# pyboard.net
KiCad netlist of a schematic drawn in EAGLE
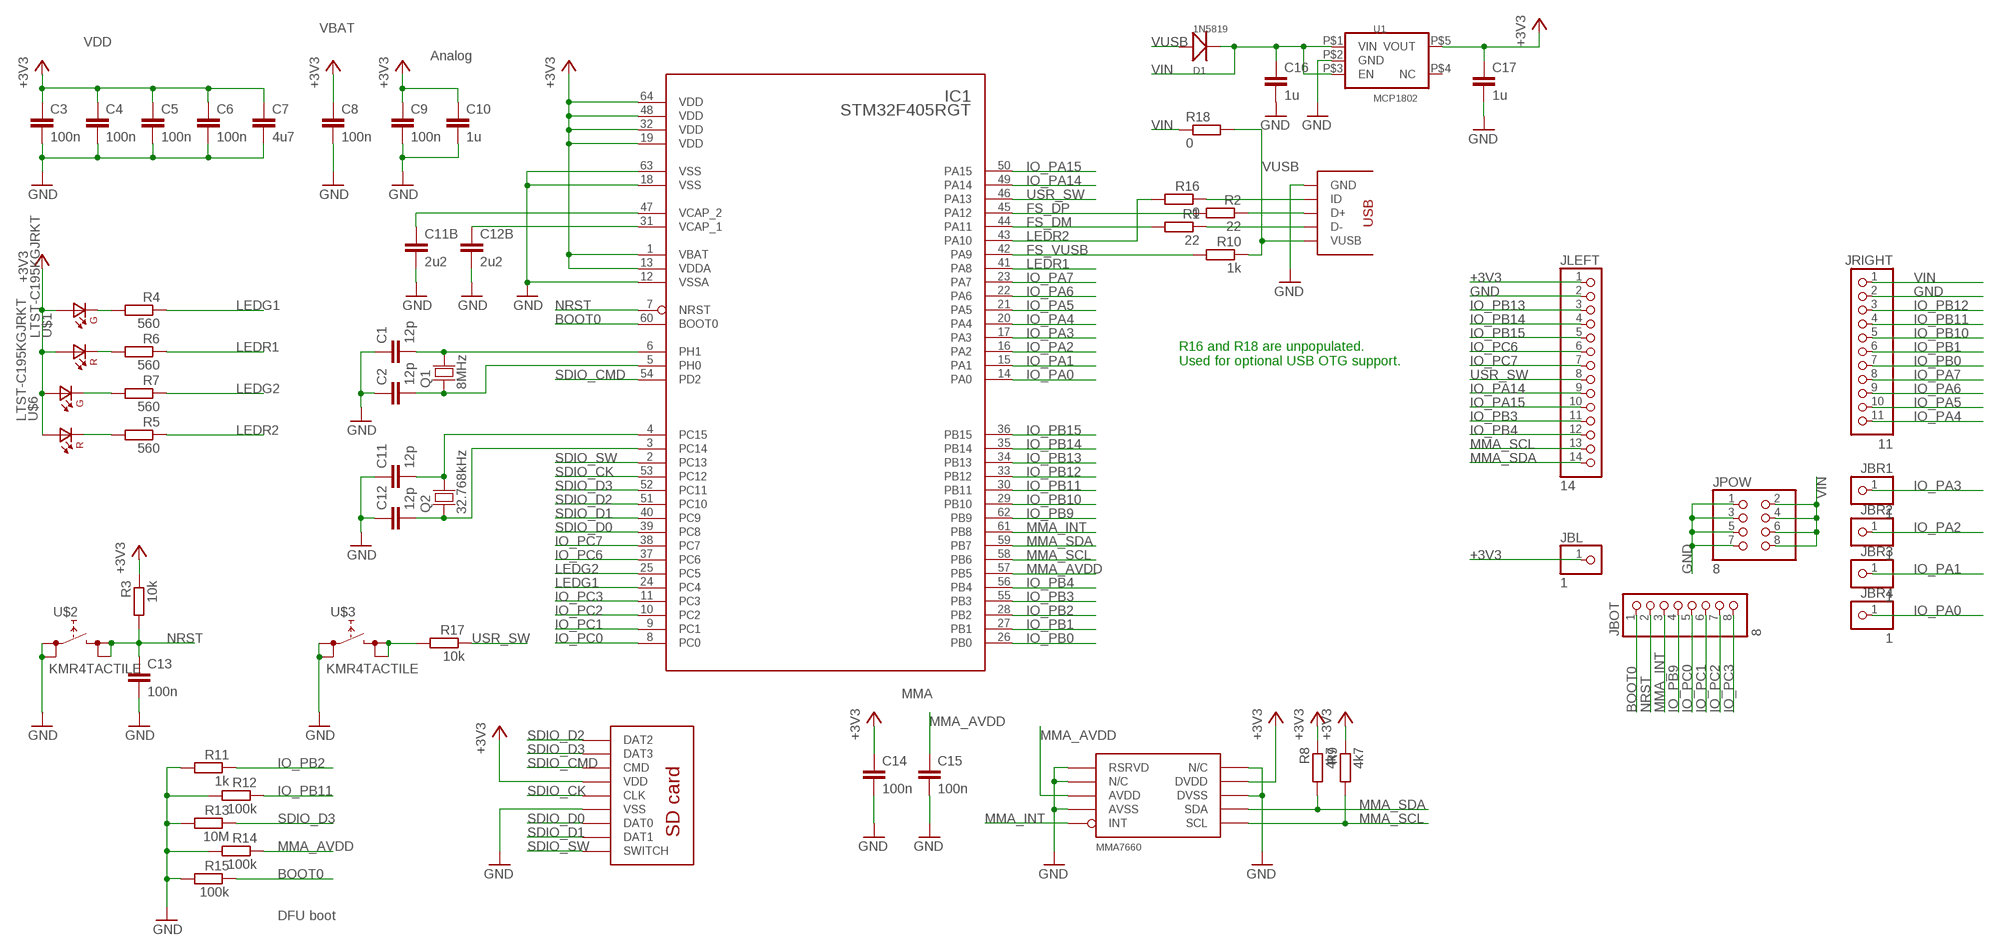
[diagram p0: schematic, sheet 1]

(export (version "E")
  (design (tool "Eeschema 10.0.6"))
  (components
    (comp (ref "C1")
      (value "12p")
      (footprint "eagle-import:C0603")
      (libsource (lib "eagle-import") (part "C-EUC0603"))
    )
    (comp (ref "C2")
      (value "12p")
      (footprint "eagle-import:C0603")
      (libsource (lib "eagle-import") (part "C-EUC0603"))
    )
    (comp (ref "C3")
      (value "100n")
      (footprint "eagle-import:C0603")
      (libsource (lib "eagle-import") (part "C-EUC0603"))
    )
    (comp (ref "C4")
      (value "100n")
      (footprint "eagle-import:C0603")
      (libsource (lib "eagle-import") (part "C-EUC0603"))
    )
    (comp (ref "C5")
      (value "100n")
      (footprint "eagle-import:C0603")
      (libsource (lib "eagle-import") (part "C-EUC0603"))
    )
    (comp (ref "C6")
      (value "100n")
      (footprint "eagle-import:C0603")
      (libsource (lib "eagle-import") (part "C-EUC0603"))
    )
    (comp (ref "C7")
      (value "4u7")
      (footprint "eagle-import:C0603")
      (libsource (lib "eagle-import") (part "C-EUC0603"))
    )
    (comp (ref "C8")
      (value "100n")
      (footprint "eagle-import:C0603")
      (libsource (lib "eagle-import") (part "C-EUC0603"))
    )
    (comp (ref "C9")
      (value "100n")
      (footprint "eagle-import:C0603")
      (libsource (lib "eagle-import") (part "C-EUC0603"))
    )
    (comp (ref "C10")
      (value "1u")
      (footprint "eagle-import:C0603")
      (libsource (lib "eagle-import") (part "C-EUC0603"))
    )
    (comp (ref "C11")
      (value "12p")
      (footprint "eagle-import:C0603")
      (libsource (lib "eagle-import") (part "C-EUC0603"))
    )
    (comp (ref "C11B")
      (value "2u2")
      (footprint "eagle-import:C0603")
      (libsource (lib "eagle-import") (part "C-EUC0603"))
    )
    (comp (ref "C12")
      (value "12p")
      (footprint "eagle-import:C0603")
      (libsource (lib "eagle-import") (part "C-EUC0603"))
    )
    (comp (ref "C12B")
      (value "2u2")
      (footprint "eagle-import:C0603")
      (libsource (lib "eagle-import") (part "C-EUC0603"))
    )
    (comp (ref "C13")
      (value "100n")
      (footprint "eagle-import:C0603")
      (libsource (lib "eagle-import") (part "C-EUC0603"))
    )
    (comp (ref "C14")
      (value "100n")
      (footprint "eagle-import:C0603")
      (libsource (lib "eagle-import") (part "C-EUC0603"))
    )
    (comp (ref "C15")
      (value "100n")
      (footprint "eagle-import:C0603")
      (libsource (lib "eagle-import") (part "C-EUC0603"))
    )
    (comp (ref "C16")
      (value "1u")
      (footprint "eagle-import:C0603")
      (libsource (lib "eagle-import") (part "C-EUC0603"))
    )
    (comp (ref "C17")
      (value "1u")
      (footprint "eagle-import:C0603")
      (libsource (lib "eagle-import") (part "C-EUC0603"))
    )
    (comp (ref "D1")
      (value "1N5819")
      (footprint "eagle-import:SOD-123")
      (libsource (lib "eagle-import") (part "1N5819"))
    )
    (comp (ref "IC1")
      (value "STM32F405RGT")
      (footprint "eagle-import:LQFP64")
      (libsource (lib "eagle-import") (part "STM32F405RTG"))
    )
    (comp (ref "JBL")
      (value "1")
      (footprint "eagle-import:1X01")
      (libsource (lib "eagle-import") (part "PINHD-1X1"))
    )
    (comp (ref "JBOT")
      (value "8")
      (footprint "eagle-import:1X08")
      (libsource (lib "eagle-import") (part "PINHD-1X8"))
    )
    (comp (ref "JBR1")
      (value "1")
      (footprint "eagle-import:1X01")
      (libsource (lib "eagle-import") (part "PINHD-1X1"))
    )
    (comp (ref "JBR2")
      (value "1")
      (footprint "eagle-import:1X01")
      (libsource (lib "eagle-import") (part "PINHD-1X1"))
    )
    (comp (ref "JBR3")
      (value "1")
      (footprint "eagle-import:1X01")
      (libsource (lib "eagle-import") (part "PINHD-1X1"))
    )
    (comp (ref "JBR4")
      (value "1")
      (footprint "eagle-import:1X01")
      (libsource (lib "eagle-import") (part "PINHD-1X1"))
    )
    (comp (ref "JLEFT")
      (value "14")
      (footprint "eagle-import:1X14")
      (libsource (lib "eagle-import") (part "PINHD-1X14"))
    )
    (comp (ref "JPOW")
      (value "8")
      (footprint "eagle-import:2X04")
      (libsource (lib "eagle-import") (part "PINHD-2X4"))
    )
    (comp (ref "JRIGHT")
      (value "11")
      (footprint "eagle-import:1X11")
      (libsource (lib "eagle-import") (part "PINHD-1X11"))
    )
    (comp (ref "Q1")
      (value "8MHz")
      (footprint "eagle-import:TXC-SMD-50X32")
      (libsource (lib "eagle-import") (part "TXC-CRYSTAL50X32"))
    )
    (comp (ref "Q2")
      (value "32.768kHz")
      (footprint "eagle-import:TXC-SMD-32X15")
      (libsource (lib "eagle-import") (part "TXC-CRYSTAL32X15"))
    )
    (comp (ref "R1")
      (value "22")
      (footprint "eagle-import:R0603")
      (libsource (lib "eagle-import") (part "R-EU_R0603"))
    )
    (comp (ref "R2")
      (value "22")
      (footprint "eagle-import:R0603")
      (libsource (lib "eagle-import") (part "R-EU_R0603"))
    )
    (comp (ref "R3")
      (value "10k")
      (footprint "eagle-import:R0603")
      (libsource (lib "eagle-import") (part "R-EU_R0603"))
    )
    (comp (ref "R4")
      (value "560")
      (footprint "eagle-import:R0603")
      (libsource (lib "eagle-import") (part "R-EU_R0603"))
    )
    (comp (ref "R5")
      (value "560")
      (footprint "eagle-import:R0603")
      (libsource (lib "eagle-import") (part "R-EU_R0603"))
    )
    (comp (ref "R6")
      (value "560")
      (footprint "eagle-import:R0603")
      (libsource (lib "eagle-import") (part "R-EU_R0603"))
    )
    (comp (ref "R7")
      (value "560")
      (footprint "eagle-import:R0603")
      (libsource (lib "eagle-import") (part "R-EU_R0603"))
    )
    (comp (ref "R8")
      (value "4k7")
      (footprint "eagle-import:R0603")
      (libsource (lib "eagle-import") (part "R-EU_R0603"))
    )
    (comp (ref "R9")
      (value "4k7")
      (footprint "eagle-import:R0603")
      (libsource (lib "eagle-import") (part "R-EU_R0603"))
    )
    (comp (ref "R10")
      (value "1k")
      (footprint "eagle-import:R0603")
      (libsource (lib "eagle-import") (part "R-EU_R0603"))
    )
    (comp (ref "R11")
      (value "1k")
      (footprint "eagle-import:R0603")
      (libsource (lib "eagle-import") (part "R-EU_R0603"))
    )
    (comp (ref "R12")
      (value "100k")
      (footprint "eagle-import:R0603")
      (libsource (lib "eagle-import") (part "R-EU_R0603"))
    )
    (comp (ref "R13")
      (value "10M")
      (footprint "eagle-import:R0603")
      (libsource (lib "eagle-import") (part "R-EU_R0603"))
    )
    (comp (ref "R14")
      (value "100k")
      (footprint "eagle-import:R0603")
      (libsource (lib "eagle-import") (part "R-EU_R0603"))
    )
    (comp (ref "R15")
      (value "100k")
      (footprint "eagle-import:R0603")
      (libsource (lib "eagle-import") (part "R-EU_R0603"))
    )
    (comp (ref "R16")
      (value "0")
      (footprint "eagle-import:R0603")
      (libsource (lib "eagle-import") (part "R-EU_R0603"))
    )
    (comp (ref "R17")
      (value "10k")
      (footprint "eagle-import:R0603")
      (libsource (lib "eagle-import") (part "R-EU_R0603"))
    )
    (comp (ref "R18")
      (value "0")
      (footprint "eagle-import:R0805")
      (libsource (lib "eagle-import") (part "R-EU_R0805"))
    )
    (comp (ref "U$1")
      (value "LTST-C195KGJRKT")
      (footprint "eagle-import:LTST-BILED-15X16")
      (libsource (lib "eagle-import") (part "LTST-C195KGJRKT"))
    )
    (comp (ref "U$2")
      (value "KMR4TACTILE")
      (footprint "eagle-import:KMR4SWITCH")
      (libsource (lib "eagle-import") (part "KMR4TACTILE"))
    )
    (comp (ref "U$3")
      (value "KMR4TACTILE")
      (footprint "eagle-import:KMR4SWITCH")
      (libsource (lib "eagle-import") (part "KMR4TACTILE"))
    )
    (comp (ref "U$4")
      (value "MOLEX-SD-105027")
      (footprint "eagle-import:MOLEX-SD-105027-PKG")
      (libsource (lib "eagle-import") (part "MOLEX-SD-105027"))
    )
    (comp (ref "U$5")
      (value "MMA7660")
      (footprint "eagle-import:DFN10")
      (libsource (lib "eagle-import") (part "MMA7660"))
    )
    (comp (ref "U$6")
      (value "LTST-C195KGJRKT")
      (footprint "eagle-import:LTST-BILED-15X16")
      (libsource (lib "eagle-import") (part "LTST-C195KGJRKT"))
    )
    (comp (ref "U$7")
      (value "USB-MICRO-AB")
      (footprint "eagle-import:HRS-USB-ZX62D-AB-5P8-PKG")
      (libsource (lib "eagle-import") (part "USB-MICRO-AB"))
    )
    (comp (ref "U1")
      (value "MCP1802")
      (footprint "eagle-import:SOT-23-5")
      (libsource (lib "eagle-import") (part "MCP1802"))
    )
  )
  (nets
    (net (code "1") (name "+3V3") (class "Default")
      (node (ref "C10") (pin "1") (pinfunction "1_1") (pintype "passive"))
      (node (ref "C14") (pin "1") (pinfunction "1_1") (pintype "passive"))
      (node (ref "C17") (pin "1") (pinfunction "1_1") (pintype "passive"))
      (node (ref "C3") (pin "1") (pinfunction "1_1") (pintype "passive"))
      (node (ref "C4") (pin "1") (pinfunction "1_1") (pintype "passive"))
      (node (ref "C5") (pin "1") (pinfunction "1_1") (pintype "passive"))
      (node (ref "C6") (pin "1") (pinfunction "1_1") (pintype "passive"))
      (node (ref "C7") (pin "1") (pinfunction "1_1") (pintype "passive"))
      (node (ref "C8") (pin "1") (pinfunction "1_1") (pintype "passive"))
      (node (ref "C9") (pin "1") (pinfunction "1_1") (pintype "passive"))
      (node (ref "IC1") (pin "1") (pinfunction "VBAT_1") (pintype "power_in"))
      (node (ref "IC1") (pin "13") (pinfunction "VDDA_13") (pintype "power_in"))
      (node (ref "IC1") (pin "19") (pinfunction "VDD_19") (pintype "power_in"))
      (node (ref "IC1") (pin "32") (pinfunction "VDD_32") (pintype "power_in"))
      (node (ref "IC1") (pin "48") (pinfunction "VDD_48") (pintype "power_in"))
      (node (ref "IC1") (pin "64") (pinfunction "VDD_64") (pintype "power_in"))
      (node (ref "JBL") (pin "1") (pinfunction "1_1") (pintype "passive"))
      (node (ref "JLEFT") (pin "1") (pinfunction "1_1") (pintype "passive"))
      (node (ref "R3") (pin "1") (pinfunction "1_1") (pintype "passive"))
      (node (ref "R8") (pin "1") (pinfunction "1_1") (pintype "passive"))
      (node (ref "R9") (pin "1") (pinfunction "1_1") (pintype "passive"))
      (node (ref "U$1") (pin "P$1") (pinfunction "A1_P$1") (pintype "passive"))
      (node (ref "U$1") (pin "P$2") (pinfunction "A2_P$2") (pintype "passive"))
      (node (ref "U$4") (pin "P$4") (pinfunction "VDD_P$4") (pintype "bidirectional"))
      (node (ref "U$5") (pin "P$9") (pinfunction "DVDD_P$9") (pintype "power_in"))
      (node (ref "U$6") (pin "P$1") (pinfunction "A1_P$1") (pintype "passive"))
      (node (ref "U$6") (pin "P$2") (pinfunction "A2_P$2") (pintype "passive"))
      (node (ref "U1") (pin "P$5") (pinfunction "VOUT_P$5") (pintype "power_in"))
    )
    (net (code "2") (name "/BOOT0") (class "Default")
      (node (ref "IC1") (pin "60") (pinfunction "BOOT0_60") (pintype "bidirectional"))
      (node (ref "JBOT") (pin "1") (pinfunction "1_1") (pintype "passive"))
      (node (ref "R15") (pin "1") (pinfunction "1_1") (pintype "passive"))
    )
    (net (code "3") (name "/FS_DM") (class "Default")
      (node (ref "IC1") (pin "44") (pinfunction "PA11_44") (pintype "bidirectional"))
      (node (ref "R1") (pin "2") (pinfunction "2_2") (pintype "passive"))
    )
    (net (code "4") (name "/FS_DP") (class "Default")
      (node (ref "IC1") (pin "45") (pinfunction "PA12_45") (pintype "bidirectional"))
      (node (ref "R2") (pin "2") (pinfunction "2_2") (pintype "passive"))
    )
    (net (code "5") (name "/FS_VUSB") (class "Default")
      (node (ref "IC1") (pin "42") (pinfunction "PA9_42") (pintype "bidirectional"))
      (node (ref "R10") (pin "2") (pinfunction "2_2") (pintype "passive"))
    )
    (net (code "6") (name "/IO_PA0") (class "Default")
      (node (ref "IC1") (pin "14") (pinfunction "PA0_14") (pintype "bidirectional"))
      (node (ref "JBR4") (pin "1") (pinfunction "1_1") (pintype "passive"))
    )
    (net (code "7") (name "/IO_PA1") (class "Default")
      (node (ref "IC1") (pin "15") (pinfunction "PA1_15") (pintype "bidirectional"))
      (node (ref "JBR3") (pin "1") (pinfunction "1_1") (pintype "passive"))
    )
    (net (code "8") (name "/IO_PA2") (class "Default")
      (node (ref "IC1") (pin "16") (pinfunction "PA2_16") (pintype "bidirectional"))
      (node (ref "JBR2") (pin "1") (pinfunction "1_1") (pintype "passive"))
    )
    (net (code "9") (name "/IO_PA3") (class "Default")
      (node (ref "IC1") (pin "17") (pinfunction "PA3_17") (pintype "bidirectional"))
      (node (ref "JBR1") (pin "1") (pinfunction "1_1") (pintype "passive"))
    )
    (net (code "10") (name "/IO_PA4") (class "Default")
      (node (ref "IC1") (pin "20") (pinfunction "PA4_20") (pintype "bidirectional"))
      (node (ref "JRIGHT") (pin "11") (pinfunction "11_11") (pintype "passive"))
    )
    (net (code "11") (name "/IO_PA5") (class "Default")
      (node (ref "IC1") (pin "21") (pinfunction "PA5_21") (pintype "bidirectional"))
      (node (ref "JRIGHT") (pin "10") (pinfunction "10_10") (pintype "passive"))
    )
    (net (code "12") (name "/IO_PA6") (class "Default")
      (node (ref "IC1") (pin "22") (pinfunction "PA6_22") (pintype "bidirectional"))
      (node (ref "JRIGHT") (pin "9") (pinfunction "9_9") (pintype "passive"))
    )
    (net (code "13") (name "/IO_PA7") (class "Default")
      (node (ref "IC1") (pin "23") (pinfunction "PA7_23") (pintype "bidirectional"))
      (node (ref "JRIGHT") (pin "8") (pinfunction "8_8") (pintype "passive"))
    )
    (net (code "14") (name "/IO_PA14") (class "Default")
      (node (ref "IC1") (pin "49") (pinfunction "PA14_49") (pintype "bidirectional"))
      (node (ref "JLEFT") (pin "9") (pinfunction "9_9") (pintype "passive"))
    )
    (net (code "15") (name "/IO_PA15") (class "Default")
      (node (ref "IC1") (pin "50") (pinfunction "PA15_50") (pintype "bidirectional"))
      (node (ref "JLEFT") (pin "10") (pinfunction "10_10") (pintype "passive"))
    )
    (net (code "16") (name "/IO_PB0") (class "Default")
      (node (ref "IC1") (pin "26") (pinfunction "PB0_26") (pintype "bidirectional"))
      (node (ref "JRIGHT") (pin "7") (pinfunction "7_7") (pintype "passive"))
    )
    (net (code "17") (name "/IO_PB1") (class "Default")
      (node (ref "IC1") (pin "27") (pinfunction "PB1_27") (pintype "bidirectional"))
      (node (ref "JRIGHT") (pin "6") (pinfunction "6_6") (pintype "passive"))
    )
    (net (code "18") (name "/IO_PB2") (class "Default")
      (node (ref "IC1") (pin "28") (pinfunction "PB2_28") (pintype "bidirectional"))
      (node (ref "R11") (pin "1") (pinfunction "1_1") (pintype "passive"))
    )
    (net (code "19") (name "/IO_PB3") (class "Default")
      (node (ref "IC1") (pin "55") (pinfunction "PB3_55") (pintype "bidirectional"))
      (node (ref "JLEFT") (pin "11") (pinfunction "11_11") (pintype "passive"))
    )
    (net (code "20") (name "/IO_PB4") (class "Default")
      (node (ref "IC1") (pin "56") (pinfunction "PB4_56") (pintype "bidirectional"))
      (node (ref "JLEFT") (pin "12") (pinfunction "12_12") (pintype "passive"))
    )
    (net (code "21") (name "/IO_PB9") (class "Default")
      (node (ref "IC1") (pin "62") (pinfunction "PB9_62") (pintype "bidirectional"))
      (node (ref "JBOT") (pin "4") (pinfunction "4_4") (pintype "passive"))
    )
    (net (code "22") (name "/IO_PB10") (class "Default")
      (node (ref "IC1") (pin "29") (pinfunction "PB10_29") (pintype "bidirectional"))
      (node (ref "JRIGHT") (pin "5") (pinfunction "5_5") (pintype "passive"))
    )
    (net (code "23") (name "/IO_PB11") (class "Default")
      (node (ref "IC1") (pin "30") (pinfunction "PB11_30") (pintype "bidirectional"))
      (node (ref "JRIGHT") (pin "4") (pinfunction "4_4") (pintype "passive"))
      (node (ref "R12") (pin "1") (pinfunction "1_1") (pintype "passive"))
    )
    (net (code "24") (name "/IO_PB12") (class "Default")
      (node (ref "IC1") (pin "33") (pinfunction "PB12_33") (pintype "bidirectional"))
      (node (ref "JRIGHT") (pin "3") (pinfunction "3_3") (pintype "passive"))
    )
    (net (code "25") (name "/IO_PB13") (class "Default")
      (node (ref "IC1") (pin "34") (pinfunction "PB13_34") (pintype "bidirectional"))
      (node (ref "JLEFT") (pin "3") (pinfunction "3_3") (pintype "passive"))
    )
    (net (code "26") (name "/IO_PB14") (class "Default")
      (node (ref "IC1") (pin "35") (pinfunction "PB14_35") (pintype "bidirectional"))
      (node (ref "JLEFT") (pin "4") (pinfunction "4_4") (pintype "passive"))
    )
    (net (code "27") (name "/IO_PB15") (class "Default")
      (node (ref "IC1") (pin "36") (pinfunction "PB15_36") (pintype "bidirectional"))
      (node (ref "JLEFT") (pin "5") (pinfunction "5_5") (pintype "passive"))
    )
    (net (code "28") (name "/IO_PC0") (class "Default")
      (node (ref "IC1") (pin "8") (pinfunction "PC0_8") (pintype "bidirectional"))
      (node (ref "JBOT") (pin "5") (pinfunction "5_5") (pintype "passive"))
    )
    (net (code "29") (name "/IO_PC1") (class "Default")
      (node (ref "IC1") (pin "9") (pinfunction "PC1_9") (pintype "bidirectional"))
      (node (ref "JBOT") (pin "6") (pinfunction "6_6") (pintype "passive"))
    )
    (net (code "30") (name "/IO_PC2") (class "Default")
      (node (ref "IC1") (pin "10") (pinfunction "PC2_10") (pintype "bidirectional"))
      (node (ref "JBOT") (pin "7") (pinfunction "7_7") (pintype "passive"))
    )
    (net (code "31") (name "/IO_PC3") (class "Default")
      (node (ref "IC1") (pin "11") (pinfunction "PC3_11") (pintype "bidirectional"))
      (node (ref "JBOT") (pin "8") (pinfunction "8_8") (pintype "passive"))
    )
    (net (code "32") (name "/IO_PC6") (class "Default")
      (node (ref "IC1") (pin "37") (pinfunction "PC6_37") (pintype "bidirectional"))
      (node (ref "JLEFT") (pin "6") (pinfunction "6_6") (pintype "passive"))
    )
    (net (code "33") (name "/IO_PC7") (class "Default")
      (node (ref "IC1") (pin "38") (pinfunction "PC7_38") (pintype "bidirectional"))
      (node (ref "JLEFT") (pin "7") (pinfunction "7_7") (pintype "passive"))
    )
    (net (code "34") (name "/LEDG1") (class "Default")
      (node (ref "IC1") (pin "24") (pinfunction "PC4_24") (pintype "bidirectional"))
      (node (ref "R4") (pin "1") (pinfunction "1_1") (pintype "passive"))
    )
    (net (code "35") (name "/LEDG2") (class "Default")
      (node (ref "IC1") (pin "25") (pinfunction "PC5_25") (pintype "bidirectional"))
      (node (ref "R7") (pin "1") (pinfunction "1_1") (pintype "passive"))
    )
    (net (code "36") (name "/LEDR1") (class "Default")
      (node (ref "IC1") (pin "41") (pinfunction "PA8_41") (pintype "bidirectional"))
      (node (ref "R6") (pin "1") (pinfunction "1_1") (pintype "passive"))
    )
    (net (code "37") (name "/LEDR2") (class "Default")
      (node (ref "IC1") (pin "43") (pinfunction "PA10_43") (pintype "bidirectional"))
      (node (ref "R16") (pin "2") (pinfunction "2_2") (pintype "passive"))
      (node (ref "R5") (pin "1") (pinfunction "1_1") (pintype "passive"))
    )
    (net (code "38") (name "/MMA_AVDD") (class "Default")
      (node (ref "C15") (pin "1") (pinfunction "1_1") (pintype "passive"))
      (node (ref "IC1") (pin "57") (pinfunction "PB5_57") (pintype "bidirectional"))
      (node (ref "R14") (pin "1") (pinfunction "1_1") (pintype "passive"))
      (node (ref "U$5") (pin "P$3") (pinfunction "AVDD_P$3") (pintype "power_in"))
    )
    (net (code "39") (name "/MMA_INT") (class "Default")
      (node (ref "IC1") (pin "61") (pinfunction "PB8_61") (pintype "bidirectional"))
      (node (ref "JBOT") (pin "3") (pinfunction "3_3") (pintype "passive"))
      (node (ref "U$5") (pin "P$5") (pinfunction "INT_P$5") (pintype "output"))
    )
    (net (code "40") (name "/MMA_SCL") (class "Default")
      (node (ref "IC1") (pin "58") (pinfunction "PB6_58") (pintype "bidirectional"))
      (node (ref "JLEFT") (pin "13") (pinfunction "13_13") (pintype "passive"))
      (node (ref "R9") (pin "2") (pinfunction "2_2") (pintype "passive"))
      (node (ref "U$5") (pin "P$6") (pinfunction "SCL_P$6") (pintype "input"))
    )
    (net (code "41") (name "/MMA_SDA") (class "Default")
      (node (ref "IC1") (pin "59") (pinfunction "PB7_59") (pintype "bidirectional"))
      (node (ref "JLEFT") (pin "14") (pinfunction "14_14") (pintype "passive"))
      (node (ref "R8") (pin "2") (pinfunction "2_2") (pintype "passive"))
      (node (ref "U$5") (pin "P$7") (pinfunction "SDA_P$7") (pintype "output"))
    )
    (net (code "42") (name "/NRST") (class "Default")
      (node (ref "C13") (pin "1") (pinfunction "1_1") (pintype "passive"))
      (node (ref "IC1") (pin "7") (pinfunction "NRST_7") (pintype "input"))
      (node (ref "JBOT") (pin "2") (pinfunction "2_2") (pintype "passive"))
      (node (ref "R3") (pin "2") (pinfunction "2_2") (pintype "passive"))
      (node (ref "U$2") (pin "P$3") (pinfunction "1_P$3") (pintype "passive"))
      (node (ref "U$2") (pin "P$4") (pinfunction "1_P$4") (pintype "passive"))
    )
    (net (code "43") (name "/SDIO_CK") (class "Default")
      (node (ref "IC1") (pin "53") (pinfunction "PC12_53") (pintype "bidirectional"))
      (node (ref "U$4") (pin "P$5") (pinfunction "CLK_P$5") (pintype "bidirectional"))
    )
    (net (code "44") (name "/SDIO_CMD") (class "Default")
      (node (ref "IC1") (pin "54") (pinfunction "PD2_54") (pintype "bidirectional"))
      (node (ref "U$4") (pin "P$3") (pinfunction "CMD_P$3") (pintype "bidirectional"))
    )
    (net (code "45") (name "/SDIO_D0") (class "Default")
      (node (ref "IC1") (pin "39") (pinfunction "PC8_39") (pintype "bidirectional"))
      (node (ref "U$4") (pin "P$7") (pinfunction "DAT0_P$7") (pintype "bidirectional"))
    )
    (net (code "46") (name "/SDIO_D1") (class "Default")
      (node (ref "IC1") (pin "40") (pinfunction "PC9_40") (pintype "bidirectional"))
      (node (ref "U$4") (pin "P$8") (pinfunction "DAT1_P$8") (pintype "bidirectional"))
    )
    (net (code "47") (name "/SDIO_D2") (class "Default")
      (node (ref "IC1") (pin "51") (pinfunction "PC10_51") (pintype "bidirectional"))
      (node (ref "U$4") (pin "P$1") (pinfunction "DAT2_P$1") (pintype "bidirectional"))
    )
    (net (code "48") (name "/SDIO_D3") (class "Default")
      (node (ref "IC1") (pin "52") (pinfunction "PC11_52") (pintype "bidirectional"))
      (node (ref "R13") (pin "1") (pinfunction "1_1") (pintype "passive"))
      (node (ref "U$4") (pin "P$2") (pinfunction "DAT3_P$2") (pintype "bidirectional"))
    )
    (net (code "49") (name "/SDIO_SW") (class "Default")
      (node (ref "IC1") (pin "2") (pinfunction "PC13_2") (pintype "bidirectional"))
      (node (ref "U$4") (pin "G$1") (pinfunction "SWITCH_G$1") (pintype "bidirectional"))
    )
    (net (code "50") (name "/USR_SW") (class "Default")
      (node (ref "IC1") (pin "46") (pinfunction "PA13_46") (pintype "bidirectional"))
      (node (ref "JLEFT") (pin "8") (pinfunction "8_8") (pintype "passive"))
      (node (ref "R17") (pin "1") (pinfunction "1_1") (pintype "passive"))
    )
    (net (code "51") (name "/VIN") (class "Default")
      (node (ref "C16") (pin "1") (pinfunction "1_1") (pintype "passive"))
      (node (ref "D1") (pin "K") (pinfunction "K_K") (pintype "passive"))
      (node (ref "JPOW") (pin "2") (pinfunction "2_2") (pintype "passive"))
      (node (ref "JPOW") (pin "4") (pinfunction "4_4") (pintype "passive"))
      (node (ref "JPOW") (pin "6") (pinfunction "6_6") (pintype "passive"))
      (node (ref "JPOW") (pin "8") (pinfunction "8_8") (pintype "passive"))
      (node (ref "JRIGHT") (pin "1") (pinfunction "1_1") (pintype "passive"))
      (node (ref "R18") (pin "1") (pinfunction "1_1") (pintype "passive"))
      (node (ref "U1") (pin "P$1") (pinfunction "VIN_P$1") (pintype "power_in"))
      (node (ref "U1") (pin "P$3") (pinfunction "EN_P$3") (pintype "input"))
    )
    (net (code "52") (name "/VUSB") (class "Default")
      (node (ref "D1") (pin "A") (pinfunction "A_A") (pintype "passive"))
      (node (ref "R10") (pin "1") (pinfunction "1_1") (pintype "passive"))
      (node (ref "R18") (pin "2") (pinfunction "2_2") (pintype "passive"))
      (node (ref "U$7") (pin "P$1") (pinfunction "VUSB_P$1") (pintype "power_in"))
    )
    (net (code "53") (name "GND") (class "Default")
      (node (ref "C1") (pin "1") (pinfunction "1_1") (pintype "passive"))
      (node (ref "C10") (pin "2") (pinfunction "2_2") (pintype "passive"))
      (node (ref "C11") (pin "1") (pinfunction "1_1") (pintype "passive"))
      (node (ref "C11B") (pin "2") (pinfunction "2_2") (pintype "passive"))
      (node (ref "C12") (pin "1") (pinfunction "1_1") (pintype "passive"))
      (node (ref "C12B") (pin "2") (pinfunction "2_2") (pintype "passive"))
      (node (ref "C13") (pin "2") (pinfunction "2_2") (pintype "passive"))
      (node (ref "C14") (pin "2") (pinfunction "2_2") (pintype "passive"))
      (node (ref "C15") (pin "2") (pinfunction "2_2") (pintype "passive"))
      (node (ref "C16") (pin "2") (pinfunction "2_2") (pintype "passive"))
      (node (ref "C17") (pin "2") (pinfunction "2_2") (pintype "passive"))
      (node (ref "C2") (pin "1") (pinfunction "1_1") (pintype "passive"))
      (node (ref "C3") (pin "2") (pinfunction "2_2") (pintype "passive"))
      (node (ref "C4") (pin "2") (pinfunction "2_2") (pintype "passive"))
      (node (ref "C5") (pin "2") (pinfunction "2_2") (pintype "passive"))
      (node (ref "C6") (pin "2") (pinfunction "2_2") (pintype "passive"))
      (node (ref "C7") (pin "2") (pinfunction "2_2") (pintype "passive"))
      (node (ref "C8") (pin "2") (pinfunction "2_2") (pintype "passive"))
      (node (ref "C9") (pin "2") (pinfunction "2_2") (pintype "passive"))
      (node (ref "IC1") (pin "12") (pinfunction "VSSA_12") (pintype "power_in"))
      (node (ref "IC1") (pin "18") (pinfunction "VSS_18") (pintype "power_in"))
      (node (ref "IC1") (pin "63") (pinfunction "VSS_63") (pintype "power_in"))
      (node (ref "JLEFT") (pin "2") (pinfunction "2_2") (pintype "passive"))
      (node (ref "JPOW") (pin "1") (pinfunction "1_1") (pintype "passive"))
      (node (ref "JPOW") (pin "3") (pinfunction "3_3") (pintype "passive"))
      (node (ref "JPOW") (pin "5") (pinfunction "5_5") (pintype "passive"))
      (node (ref "JPOW") (pin "7") (pinfunction "7_7") (pintype "passive"))
      (node (ref "JRIGHT") (pin "2") (pinfunction "2_2") (pintype "passive"))
      (node (ref "R11") (pin "2") (pinfunction "2_2") (pintype "passive"))
      (node (ref "R12") (pin "2") (pinfunction "2_2") (pintype "passive"))
      (node (ref "R13") (pin "2") (pinfunction "2_2") (pintype "passive"))
      (node (ref "R14") (pin "2") (pinfunction "2_2") (pintype "passive"))
      (node (ref "R15") (pin "2") (pinfunction "2_2") (pintype "passive"))
      (node (ref "U$2") (pin "P$1") (pinfunction "0_P$1") (pintype "passive"))
      (node (ref "U$2") (pin "P$2") (pinfunction "0_P$2") (pintype "passive"))
      (node (ref "U$3") (pin "P$1") (pinfunction "0_P$1") (pintype "passive"))
      (node (ref "U$3") (pin "P$2") (pinfunction "0_P$2") (pintype "passive"))
      (node (ref "U$4") (pin "P$6") (pinfunction "VSS_P$6") (pintype "bidirectional"))
      (node (ref "U$5") (pin "P$1") (pinfunction "RSRVD_P$1") (pintype "input"))
      (node (ref "U$5") (pin "P$10") (pinfunction "N/C_P$10") (pintype "input"))
      (node (ref "U$5") (pin "P$2") (pinfunction "N/C_P$2") (pintype "input"))
      (node (ref "U$5") (pin "P$4") (pinfunction "AVSS_P$4") (pintype "power_in"))
      (node (ref "U$5") (pin "P$8") (pinfunction "DVSS_P$8") (pintype "power_in"))
      (node (ref "U$7") (pin "P$5") (pinfunction "GND_P$5") (pintype "power_in"))
      (node (ref "U1") (pin "P$2") (pinfunction "GND_P$2") (pintype "power_in"))
    )
    (net (code "54") (name "Net-(IC1-PC14)") (class "Default")
      (node (ref "C12") (pin "2") (pinfunction "2_2") (pintype "passive"))
      (node (ref "IC1") (pin "3") (pinfunction "PC14_3") (pintype "bidirectional"))
      (node (ref "Q2") (pin "P$1") (pinfunction "P$1_P$1") (pintype "passive"))
    )
    (net (code "55") (name "Net-(IC1-PC15)") (class "Default")
      (node (ref "C11") (pin "2") (pinfunction "2_2") (pintype "passive"))
      (node (ref "IC1") (pin "4") (pinfunction "PC15_4") (pintype "bidirectional"))
      (node (ref "Q2") (pin "P$2") (pinfunction "P$2_P$2") (pintype "passive"))
    )
    (net (code "56") (name "Net-(IC1-PH0)") (class "Default")
      (node (ref "C2") (pin "2") (pinfunction "2_2") (pintype "passive"))
      (node (ref "IC1") (pin "5") (pinfunction "PH0_5") (pintype "bidirectional"))
      (node (ref "Q1") (pin "P$1") (pinfunction "P$1_P$1") (pintype "passive"))
    )
    (net (code "57") (name "Net-(IC1-PH1)") (class "Default")
      (node (ref "C1") (pin "2") (pinfunction "2_2") (pintype "passive"))
      (node (ref "IC1") (pin "6") (pinfunction "PH1_6") (pintype "bidirectional"))
      (node (ref "Q1") (pin "P$2") (pinfunction "P$2_P$2") (pintype "passive"))
    )
    (net (code "58") (name "Net-(IC1-VCAP_1)") (class "Default")
      (node (ref "C12B") (pin "1") (pinfunction "1_1") (pintype "passive"))
      (node (ref "IC1") (pin "31") (pinfunction "VCAP_1_31") (pintype "passive"))
    )
    (net (code "59") (name "Net-(IC1-VCAP_2)") (class "Default")
      (node (ref "C11B") (pin "1") (pinfunction "1_1") (pintype "passive"))
      (node (ref "IC1") (pin "47") (pinfunction "VCAP_2_47") (pintype "passive"))
    )
    (net (code "60") (name "Net-(R17-Pad2)") (class "Default")
      (node (ref "R17") (pin "2") (pinfunction "2_2") (pintype "passive"))
      (node (ref "U$3") (pin "P$3") (pinfunction "1_P$3") (pintype "passive"))
      (node (ref "U$3") (pin "P$4") (pinfunction "1_P$4") (pintype "passive"))
    )
    (net (code "61") (name "Net-(U$1-K1)") (class "Default")
      (node (ref "R4") (pin "2") (pinfunction "2_2") (pintype "passive"))
      (node (ref "U$1") (pin "P$3") (pinfunction "K1_P$3") (pintype "passive"))
    )
    (net (code "62") (name "Net-(U$1-K2)") (class "Default")
      (node (ref "R6") (pin "2") (pinfunction "2_2") (pintype "passive"))
      (node (ref "U$1") (pin "P$4") (pinfunction "K2_P$4") (pintype "passive"))
    )
    (net (code "63") (name "Net-(U$6-K1)") (class "Default")
      (node (ref "R7") (pin "2") (pinfunction "2_2") (pintype "passive"))
      (node (ref "U$6") (pin "P$3") (pinfunction "K1_P$3") (pintype "passive"))
    )
    (net (code "64") (name "Net-(U$6-K2)") (class "Default")
      (node (ref "R5") (pin "2") (pinfunction "2_2") (pintype "passive"))
      (node (ref "U$6") (pin "P$4") (pinfunction "K2_P$4") (pintype "passive"))
    )
    (net (code "65") (name "Net-(U$7-D+)") (class "Default")
      (node (ref "R2") (pin "1") (pinfunction "1_1") (pintype "passive"))
      (node (ref "U$7") (pin "P$3") (pinfunction "D+_P$3") (pintype "bidirectional"))
    )
    (net (code "66") (name "Net-(U$7-D-)") (class "Default")
      (node (ref "R1") (pin "1") (pinfunction "1_1") (pintype "passive"))
      (node (ref "U$7") (pin "P$2") (pinfunction "D-_P$2") (pintype "bidirectional"))
    )
    (net (code "67") (name "Net-(U$7-ID)") (class "Default")
      (node (ref "R16") (pin "1") (pinfunction "1_1") (pintype "passive"))
      (node (ref "U$7") (pin "P$4") (pinfunction "ID_P$4") (pintype "bidirectional"))
    )
    (net (code "68") (name "unconnected-(U1-NC-PadP$4)") (class "Default")
      (node (ref "U1") (pin "P$4") (pinfunction "NC_P$4") (pintype "no_connect"))
    )
  )
)
